# EMI_EMC_schematic.net
KiCad netlist of a schematic drawn in Altium Designer
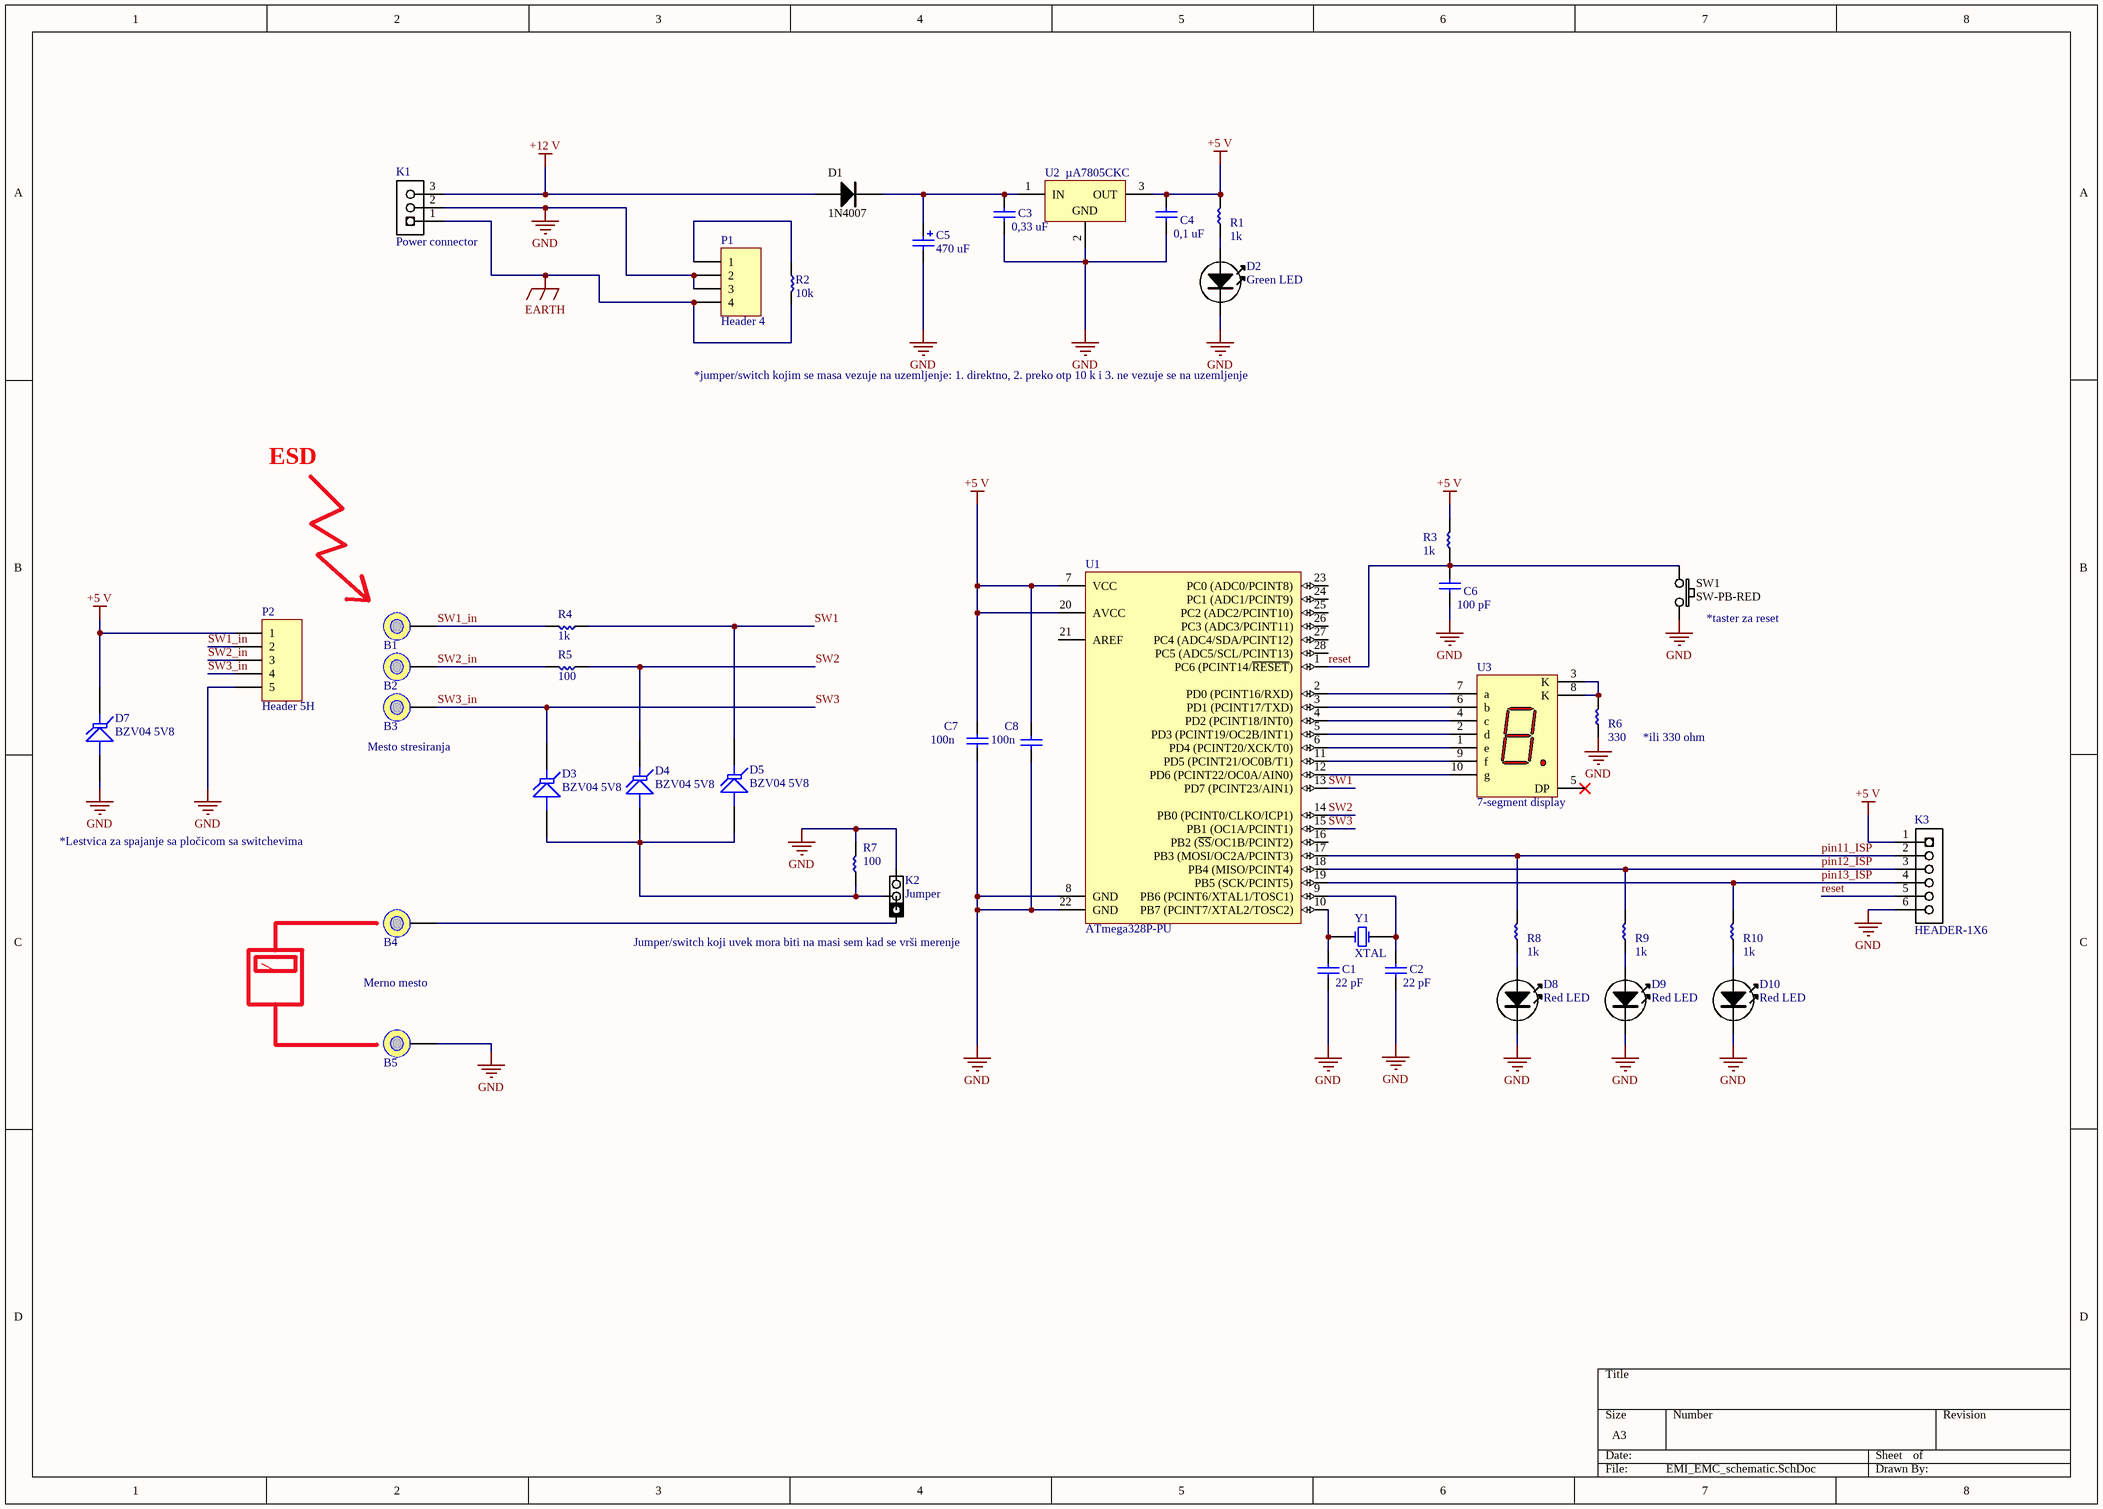
[diagram p0: EMI_EMC_schematic.SchDoc]

(export (version "E")
  (design (tool "Eeschema 10.0.6"))
  (components
    (comp (ref "B1")
      (value "Buksna 4mm")
      (footprint "Buksna 4mm")
      (libsource (lib "EMI_SCH_lib") (part "Buksna"))
    )
    (comp (ref "B2")
      (value "Buksna 4mm")
      (footprint "Buksna 4mm")
      (libsource (lib "EMI_SCH_lib") (part "Buksna"))
    )
    (comp (ref "B3")
      (value "Buksna 4mm")
      (footprint "Buksna 4mm")
      (libsource (lib "EMI_SCH_lib") (part "Buksna"))
    )
    (comp (ref "B4")
      (value "Buksna 4mm")
      (footprint "Buksna 4mm")
      (libsource (lib "EMI_SCH_lib") (part "Buksna"))
    )
    (comp (ref "B5")
      (value "Buksna 4mm")
      (footprint "Buksna 4mm")
      (libsource (lib "EMI_SCH_lib") (part "Buksna"))
    )
    (comp (ref "C1")
      (value "22 pF")
      (footprint "Cap_100mil")
      (fields (field (name "Comment") "Cap"))
      (libsource (lib "my_library") (part "Cap"))
    )
    (comp (ref "C2")
      (value "22 pF")
      (footprint "Cap_100mil")
      (fields (field (name "Comment") "Cap"))
      (libsource (lib "my_library") (part "Cap"))
    )
    (comp (ref "C3")
      (value "0,33 uF")
      (footprint "Cap_100mil")
      (fields (field (name "Comment") "Cap"))
      (libsource (lib "my_library") (part "Cap"))
    )
    (comp (ref "C4")
      (value "0,1 uF")
      (footprint "Cap_100mil")
      (fields (field (name "Comment") "Cap"))
      (libsource (lib "my_library") (part "Cap"))
    )
    (comp (ref "C5")
      (value "470 uF")
      (footprint "Cap Pol 1000 uF")
      (fields (field (name "Comment") "Cap_pol"))
      (libsource (lib "EMI_SCH_lib") (part "Cap_pol"))
    )
    (comp (ref "C6")
      (value "100 pF")
      (footprint "Cap_100mil")
      (fields (field (name "Comment") "Cap"))
      (libsource (lib "my_library") (part "Cap"))
    )
    (comp (ref "C7")
      (value "100n")
      (footprint "Cap_100mil")
      (fields (field (name "Comment") "Cap"))
      (libsource (lib "my_library") (part "Cap"))
    )
    (comp (ref "C8")
      (value "100n")
      (footprint "Cap_100mil")
      (fields (field (name "Comment") "Cap"))
      (libsource (lib "my_library") (part "Cap"))
    )
    (comp (ref "D1")
      (value "1N4007")
      (footprint "1N400X")
      (description "1N4001")
      (libsource (lib "vh_altium_library") (part "1N4001"))
    )
    (comp (ref "D2")
      (value "Green LED")
      (footprint "LED-5MM-GREEN")
      (description "LED-GREEN-5MM")
      (libsource (lib "vh_altium_library") (part "LED-GREEN-5MM"))
    )
    (comp (ref "D3")
      (value "TVS diode")
      (footprint "TVS DO - 7")
      (fields (field (name "PART NAME") "BZV04 5V8"))
      (libsource (lib "EMI_SCH_lib") (part "TVS diode"))
    )
    (comp (ref "D4")
      (value "TVS diode")
      (footprint "TVS DO - 7")
      (fields (field (name "PART NAME") "BZV04 5V8"))
      (libsource (lib "EMI_SCH_lib") (part "TVS diode"))
    )
    (comp (ref "D5")
      (value "TVS diode")
      (footprint "TVS DO - 7")
      (fields (field (name "PART NAME") "BZV04 5V8"))
      (libsource (lib "EMI_SCH_lib") (part "TVS diode"))
    )
    (comp (ref "D7")
      (value "TVS diode")
      (footprint "TVS DO - 7")
      (fields (field (name "PART NAME") "BZV04 5V8"))
      (libsource (lib "EMI_SCH_lib") (part "TVS diode"))
    )
    (comp (ref "D8")
      (value "Red LED")
      (footprint "LED-5MM-RED")
      (description "LED-RED-5MM")
      (libsource (lib "vh_altium_library") (part "LED-RED-5MM"))
    )
    (comp (ref "D9")
      (value "Red LED")
      (footprint "LED-5MM-RED")
      (description "LED-RED-5MM")
      (libsource (lib "vh_altium_library") (part "LED-RED-5MM"))
    )
    (comp (ref "D10")
      (value "Red LED")
      (footprint "LED-5MM-RED")
      (description "LED-RED-5MM")
      (libsource (lib "vh_altium_library") (part "LED-RED-5MM"))
    )
    (comp (ref "K1")
      (value "Power connector")
      (footprint "Header for power")
      (libsource (lib "EMI_SCH_lib") (part "Power connector"))
    )
    (comp (ref "K2")
      (value "Jumper")
      (footprint "JMPR3-CLOSED-12")
      (description "JMPR3")
      (fields
        (field (name "MANUFACTURER") "Sullins Connector Solutions")
        (field (name "MANUFACTURER PART NUMBER") "PBC36SAAN")
      )
      (libsource (lib "TH Connectors") (part "JMPR3-12"))
    )
    (comp (ref "K3")
      (value "HEADER-1X6")
      (footprint "HEADER-1X6")
      (libsource (lib "TH Connectors") (part "HEADER-1X6"))
    )
    (comp (ref "P1")
      (value "Header 4")
      (footprint "HDR1X4")
      (description "Header, 4-Pin")
      (fields (field (name "PUBLISHER") "Altium Limited"))
      (libsource (lib "Miscellaneous Connectors") (part "Header 4"))
    )
    (comp (ref "P2")
      (value "Header 5H")
      (footprint "HDR1X5H")
      (description "Header, 5-Pin, Right Angle")
      (fields (field (name "PUBLISHER") "Altium Limited"))
      (libsource (lib "Miscellaneous Connectors") (part "Header 5H"))
    )
    (comp (ref "R1")
      (value "1k")
      (footprint "Res_axial 0.4")
      (fields (field (name "Comment") "res_0,25w"))
      (libsource (lib "my_library") (part "Res_axial0.4"))
    )
    (comp (ref "R2")
      (value "10k")
      (footprint "Res_axial 0.4")
      (fields (field (name "Comment") "res_0,25w"))
      (libsource (lib "my_library") (part "Res_axial0.4"))
    )
    (comp (ref "R3")
      (value "1k")
      (footprint "Res_axial 0.4")
      (fields (field (name "Comment") "res_0,25w"))
      (libsource (lib "my_library") (part "Res_axial0.4"))
    )
    (comp (ref "R4")
      (value "1k")
      (footprint "Res_axial 0.4")
      (fields (field (name "Comment") "res_0,25w"))
      (libsource (lib "my_library") (part "Res_axial0.4"))
    )
    (comp (ref "R5")
      (value "100")
      (footprint "Res_axial 0.4")
      (fields (field (name "Comment") "res_0,25w"))
      (libsource (lib "my_library") (part "Res_axial0.4"))
    )
    (comp (ref "R6")
      (value "330")
      (footprint "Res_axial 0.4")
      (fields (field (name "Comment") "res_0,25w"))
      (libsource (lib "my_library") (part "Res_axial0.4"))
    )
    (comp (ref "R7")
      (value "100")
      (footprint "Res_axial 0.4")
      (fields (field (name "Comment") "res_0,25w"))
      (libsource (lib "my_library") (part "Res_axial0.4"))
    )
    (comp (ref "R8")
      (value "1k")
      (footprint "Res_axial 0.4")
      (fields (field (name "Comment") "res_0,25w"))
      (libsource (lib "my_library") (part "Res_axial0.4"))
    )
    (comp (ref "R9")
      (value "1k")
      (footprint "Res_axial 0.4")
      (fields (field (name "Comment") "res_0,25w"))
      (libsource (lib "my_library") (part "Res_axial0.4"))
    )
    (comp (ref "R10")
      (value "1k")
      (footprint "Res_axial 0.4")
      (fields (field (name "Comment") "res_0,25w"))
      (libsource (lib "my_library") (part "Res_axial0.4"))
    )
    (comp (ref "SW1")
      (value "SW-PB-RED")
      (footprint "SW-PB-RED-ROUND4")
      (description "SW-D6-R / SW-DS-S / SW-14X14 / SW-7X7")
      (libsource (lib "vh_altium_library") (part "SW-PB-RED"))
    )
    (comp (ref "U1")
      (value "ATmega328P-PU")
      (footprint "28P3")
      (fields (field (name "PUBLISHER") "Altium Limited"))
      (libsource (lib "Atmel Microcontroller 8-Bit megaAVR") (part "ATmega328P-PU"))
    )
    (comp (ref "U2") (value "µA7805CKC") (footprint "TO220") (libsource (lib "my_library") (part "TO220")))
    (comp (ref "U3")
      (value "7-segment display")
      (footprint "7-segment disp")
      (libsource (lib "EMI_SCH_lib") (part "7-segment"))
    )
    (comp (ref "Y1") (value "XTAL") (footprint "xtal") (libsource (lib "EMI_SCH_lib") (part "XTAL")))
  )
  (nets
    (net (code "1") (name "+5 V") (class "Default")
      (node (ref "C4") (pin "1") (pinfunction "1_1") (pintype "passive"))
      (node (ref "C7") (pin "2") (pinfunction "2_2") (pintype "passive"))
      (node (ref "C8") (pin "2") (pinfunction "2_2") (pintype "passive"))
      (node (ref "D7") (pin "2") (pinfunction "K_2") (pintype "passive"))
      (node (ref "K3") (pin "1") (pintype "passive"))
      (node (ref "P2") (pin "1") (pinfunction "1_1") (pintype "passive"))
      (node (ref "R1") (pin "2") (pinfunction "2_2") (pintype "passive"))
      (node (ref "R3") (pin "2") (pinfunction "2_2") (pintype "passive"))
      (node (ref "U1") (pin "20") (pinfunction "AVCC_20") (pintype "power_in"))
      (node (ref "U1") (pin "7") (pinfunction "VCC_7") (pintype "power_in"))
      (node (ref "U2") (pin "3") (pinfunction "OUT_3") (pintype "power_in"))
    )
    (net (code "2") (name "+12 V") (class "Default")
      (node (ref "D1") (pin "A") (pinfunction "A_A") (pintype "passive"))
      (node (ref "K1") (pin "3") (pintype "passive"))
    )
    (net (code "3") (name "/SW1") (class "Default")
      (node (ref "D5") (pin "2") (pinfunction "K_2") (pintype "passive"))
      (node (ref "R4") (pin "1") (pinfunction "1_1") (pintype "passive"))
      (node (ref "U1") (pin "13") (pinfunction "PD7_(PCINT23/AIN1)_13") (pintype "bidirectional"))
    )
    (net (code "4") (name "/SW1_in") (class "Default")
      (node (ref "B1") (pin "1") (pinfunction "1_1") (pintype "passive"))
      (node (ref "P2") (pin "2") (pinfunction "2_2") (pintype "passive"))
      (node (ref "R4") (pin "2") (pinfunction "2_2") (pintype "passive"))
    )
    (net (code "5") (name "/SW2") (class "Default")
      (node (ref "D4") (pin "2") (pinfunction "K_2") (pintype "passive"))
      (node (ref "R5") (pin "1") (pinfunction "1_1") (pintype "passive"))
      (node (ref "U1") (pin "14") (pinfunction "PB0_(PCINT0/CLKO/ICP1)_14") (pintype "bidirectional"))
    )
    (net (code "6") (name "/SW2_in") (class "Default")
      (node (ref "B2") (pin "1") (pinfunction "1_1") (pintype "passive"))
      (node (ref "P2") (pin "3") (pinfunction "3_3") (pintype "passive"))
      (node (ref "R5") (pin "2") (pinfunction "2_2") (pintype "passive"))
    )
    (net (code "7") (name "/SW3") (class "Default")
      (node (ref "B3") (pin "1") (pinfunction "1_1") (pintype "passive"))
      (node (ref "D3") (pin "2") (pinfunction "K_2") (pintype "passive"))
      (node (ref "P2") (pin "4") (pinfunction "4_4") (pintype "passive"))
      (node (ref "U1") (pin "15") (pinfunction "PB1_(OC1A/PCINT1)_15") (pintype "bidirectional"))
    )
    (net (code "8") (name "/pin11_ISP") (class "Default")
      (node (ref "K3") (pin "2") (pintype "passive"))
      (node (ref "R8") (pin "2") (pinfunction "2_2") (pintype "passive"))
      (node (ref "U1") (pin "17") (pinfunction "PB3_(MOSI/OC2A/PCINT3)_17") (pintype "bidirectional"))
    )
    (net (code "9") (name "/pin12_ISP") (class "Default")
      (node (ref "K3") (pin "3") (pintype "passive"))
      (node (ref "R9") (pin "2") (pinfunction "2_2") (pintype "passive"))
      (node (ref "U1") (pin "18") (pinfunction "PB4_(MISO/PCINT4)_18") (pintype "bidirectional"))
    )
    (net (code "10") (name "/pin13_ISP") (class "Default")
      (node (ref "K3") (pin "4") (pintype "passive"))
      (node (ref "R10") (pin "2") (pinfunction "2_2") (pintype "passive"))
      (node (ref "U1") (pin "19") (pinfunction "PB5_(SCK/PCINT5)_19") (pintype "bidirectional"))
    )
    (net (code "11") (name "/reset") (class "Default")
      (node (ref "C6") (pin "1") (pinfunction "1_1") (pintype "passive"))
      (node (ref "K3") (pin "5") (pintype "passive"))
      (node (ref "R3") (pin "1") (pinfunction "1_1") (pintype "passive"))
      (node (ref "SW1") (pin "1") (pintype "passive"))
      (node (ref "U1") (pin "1") (pinfunction "PC6_(PCINT14/~{RESET})_1") (pintype "bidirectional"))
    )
    (net (code "12") (name "EARTH") (class "Default")
      (node (ref "K1") (pin "1") (pintype "passive"))
      (node (ref "P1") (pin "4") (pinfunction "4_4") (pintype "passive"))
      (node (ref "R2") (pin "2") (pinfunction "2_2") (pintype "passive"))
    )
    (net (code "13") (name "GND") (class "Default")
      (node (ref "B5") (pin "1") (pinfunction "1_1") (pintype "passive"))
      (node (ref "C1") (pin "2") (pinfunction "2_2") (pintype "passive"))
      (node (ref "C2") (pin "2") (pinfunction "2_2") (pintype "passive"))
      (node (ref "C3") (pin "2") (pinfunction "2_2") (pintype "passive"))
      (node (ref "C4") (pin "2") (pinfunction "2_2") (pintype "passive"))
      (node (ref "C5") (pin "2") (pinfunction "2_2") (pintype "passive"))
      (node (ref "C6") (pin "2") (pinfunction "2_2") (pintype "passive"))
      (node (ref "C7") (pin "1") (pinfunction "1_1") (pintype "passive"))
      (node (ref "C8") (pin "1") (pinfunction "1_1") (pintype "passive"))
      (node (ref "D10") (pin "K") (pintype "passive"))
      (node (ref "D2") (pin "K") (pintype "passive"))
      (node (ref "D7") (pin "1") (pinfunction "A_1") (pintype "passive"))
      (node (ref "D8") (pin "K") (pintype "passive"))
      (node (ref "D9") (pin "K") (pintype "passive"))
      (node (ref "K1") (pin "2") (pintype "passive"))
      (node (ref "K2") (pin "3") (pintype "passive"))
      (node (ref "K3") (pin "6") (pintype "passive"))
      (node (ref "P1") (pin "2") (pinfunction "2_2") (pintype "passive"))
      (node (ref "P1") (pin "3") (pinfunction "3_3") (pintype "passive"))
      (node (ref "P2") (pin "5") (pinfunction "5_5") (pintype "passive"))
      (node (ref "R6") (pin "1") (pinfunction "1_1") (pintype "passive"))
      (node (ref "R7") (pin "2") (pinfunction "2_2") (pintype "passive"))
      (node (ref "SW1") (pin "2") (pintype "passive"))
      (node (ref "U1") (pin "22") (pinfunction "GND_22") (pintype "power_in"))
      (node (ref "U1") (pin "8") (pinfunction "GND_8") (pintype "power_in"))
      (node (ref "U2") (pin "2") (pinfunction "GND_2") (pintype "power_in"))
    )
    (net (code "14") (name "Net-(B4-Pad1)") (class "Default")
      (node (ref "B4") (pin "1") (pinfunction "1_1") (pintype "passive"))
      (node (ref "K2") (pin "1") (pintype "passive"))
    )
    (net (code "15") (name "Net-(D2-PadA)") (class "Default")
      (node (ref "D2") (pin "A") (pintype "passive"))
      (node (ref "R1") (pin "1") (pinfunction "1_1") (pintype "passive"))
    )
    (net (code "16") (name "Net-(D3-A)") (class "Default")
      (node (ref "D3") (pin "1") (pinfunction "A_1") (pintype "passive"))
      (node (ref "D4") (pin "1") (pinfunction "A_1") (pintype "passive"))
      (node (ref "D5") (pin "1") (pinfunction "A_1") (pintype "passive"))
      (node (ref "K2") (pin "2") (pintype "passive"))
      (node (ref "R7") (pin "1") (pinfunction "1_1") (pintype "passive"))
    )
    (net (code "17") (name "Net-(D8-PadA)") (class "Default")
      (node (ref "D8") (pin "A") (pintype "passive"))
      (node (ref "R8") (pin "1") (pinfunction "1_1") (pintype "passive"))
    )
    (net (code "18") (name "Net-(D9-PadA)") (class "Default")
      (node (ref "D9") (pin "A") (pintype "passive"))
      (node (ref "R9") (pin "1") (pinfunction "1_1") (pintype "passive"))
    )
    (net (code "19") (name "Net-(D10-PadA)") (class "Default")
      (node (ref "D10") (pin "A") (pintype "passive"))
      (node (ref "R10") (pin "1") (pinfunction "1_1") (pintype "passive"))
    )
    (net (code "20") (name "Net-(P1-Pad1)") (class "Default")
      (node (ref "P1") (pin "1") (pinfunction "1_1") (pintype "passive"))
      (node (ref "R2") (pin "1") (pinfunction "1_1") (pintype "passive"))
    )
    (net (code "21") (name "Net-(R6-Pad2)") (class "Default")
      (node (ref "R6") (pin "2") (pinfunction "2_2") (pintype "passive"))
      (node (ref "U3") (pin "3") (pinfunction "K_3") (pintype "passive"))
      (node (ref "U3") (pin "8") (pinfunction "K_8") (pintype "passive"))
    )
    (net (code "22") (name "Net-(U1-PB6_(PCINT6{slash}XTAL1{slash}TOSC1))") (class "Default")
      (node (ref "C2") (pin "1") (pinfunction "1_1") (pintype "passive"))
      (node (ref "U1") (pin "9") (pinfunction "PB6_(PCINT6/XTAL1/TOSC1)_9") (pintype "bidirectional"))
      (node (ref "Y1") (pin "2") (pinfunction "OSC2_2") (pintype "passive"))
    )
    (net (code "23") (name "Net-(U1-PB7_(PCINT7{slash}XTAL2{slash}TOSC2))") (class "Default")
      (node (ref "C1") (pin "1") (pinfunction "1_1") (pintype "passive"))
      (node (ref "U1") (pin "10") (pinfunction "PB7_(PCINT7/XTAL2/TOSC2)_10") (pintype "bidirectional"))
      (node (ref "Y1") (pin "1") (pinfunction "OSC1_1") (pintype "passive"))
    )
    (net (code "24") (name "Net-(U1-PD0_(PCINT16{slash}RXD))") (class "Default")
      (node (ref "U1") (pin "2") (pinfunction "PD0_(PCINT16/RXD)_2") (pintype "bidirectional"))
      (node (ref "U3") (pin "7") (pinfunction "a_7") (pintype "passive"))
    )
    (net (code "25") (name "Net-(U1-PD1_(PCINT17{slash}TXD))") (class "Default")
      (node (ref "U1") (pin "3") (pinfunction "PD1_(PCINT17/TXD)_3") (pintype "bidirectional"))
      (node (ref "U3") (pin "6") (pinfunction "b_6") (pintype "passive"))
    )
    (net (code "26") (name "Net-(U1-PD2_(PCINT18{slash}INT0))") (class "Default")
      (node (ref "U1") (pin "4") (pinfunction "PD2_(PCINT18/INT0)_4") (pintype "bidirectional"))
      (node (ref "U3") (pin "4") (pinfunction "c_4") (pintype "passive"))
    )
    (net (code "27") (name "Net-(U1-PD3_(PCINT19{slash}OC2B{slash}INT1))") (class "Default")
      (node (ref "U1") (pin "5") (pinfunction "PD3_(PCINT19/OC2B/INT1)_5") (pintype "bidirectional"))
      (node (ref "U3") (pin "2") (pinfunction "d_2") (pintype "passive"))
    )
    (net (code "28") (name "Net-(U1-PD4_(PCINT20{slash}XCK{slash}T0))") (class "Default")
      (node (ref "U1") (pin "6") (pinfunction "PD4_(PCINT20/XCK/T0)_6") (pintype "bidirectional"))
      (node (ref "U3") (pin "1") (pinfunction "e_1") (pintype "passive"))
    )
    (net (code "29") (name "Net-(U1-PD5_(PCINT21{slash}OC0B{slash}T1))") (class "Default")
      (node (ref "U1") (pin "11") (pinfunction "PD5_(PCINT21/OC0B/T1)_11") (pintype "bidirectional"))
      (node (ref "U3") (pin "9") (pinfunction "f_9") (pintype "passive"))
    )
    (net (code "30") (name "Net-(U1-PD6_(PCINT22{slash}OC0A{slash}AIN0))") (class "Default")
      (node (ref "U1") (pin "12") (pinfunction "PD6_(PCINT22/OC0A/AIN0)_12") (pintype "bidirectional"))
      (node (ref "U3") (pin "10") (pinfunction "g_10") (pintype "passive"))
    )
    (net (code "31") (name "Net-(U2-IN)") (class "Default")
      (node (ref "C3") (pin "1") (pinfunction "1_1") (pintype "passive"))
      (node (ref "C5") (pin "1") (pinfunction "1_1") (pintype "passive"))
      (node (ref "D1") (pin "K") (pinfunction "K_K") (pintype "passive"))
      (node (ref "U2") (pin "1") (pinfunction "IN_1") (pintype "power_in"))
    )
    (net (code "32") (name "unconnected-(B1-Pad2)") (class "Default")
      (node (ref "B1") (pin "2") (pinfunction "2_2") (pintype "passive"))
    )
    (net (code "33") (name "unconnected-(B2-Pad2)") (class "Default")
      (node (ref "B2") (pin "2") (pinfunction "2_2") (pintype "passive"))
    )
    (net (code "34") (name "unconnected-(B3-Pad2)") (class "Default")
      (node (ref "B3") (pin "2") (pinfunction "2_2") (pintype "passive"))
    )
    (net (code "35") (name "unconnected-(B4-Pad2)") (class "Default")
      (node (ref "B4") (pin "2") (pinfunction "2_2") (pintype "passive"))
    )
    (net (code "36") (name "unconnected-(B5-Pad2)") (class "Default")
      (node (ref "B5") (pin "2") (pinfunction "2_2") (pintype "passive"))
    )
    (net (code "37") (name "unconnected-(U1-AREF-Pad21)") (class "Default")
      (node (ref "U1") (pin "21") (pinfunction "AREF_21") (pintype "power_in"))
    )
    (net (code "38") (name "unconnected-(U1-PB2_(~{SS}{slash}OC1B{slash}PCINT2)-Pad16)") (class "Default")
      (node (ref "U1") (pin "16") (pinfunction "PB2_(~{SS}/OC1B/PCINT2)_16") (pintype "bidirectional"))
    )
    (net (code "39") (name "unconnected-(U1-PC0_(ADC0{slash}PCINT8)-Pad23)") (class "Default")
      (node (ref "U1") (pin "23") (pinfunction "PC0_(ADC0/PCINT8)_23") (pintype "bidirectional"))
    )
    (net (code "40") (name "unconnected-(U1-PC1_(ADC1{slash}PCINT9)-Pad24)") (class "Default")
      (node (ref "U1") (pin "24") (pinfunction "PC1_(ADC1/PCINT9)_24") (pintype "bidirectional"))
    )
    (net (code "41") (name "unconnected-(U1-PC2_(ADC2{slash}PCINT10)-Pad25)") (class "Default")
      (node (ref "U1") (pin "25") (pinfunction "PC2_(ADC2/PCINT10)_25") (pintype "bidirectional"))
    )
    (net (code "42") (name "unconnected-(U1-PC3_(ADC3{slash}PCINT11)-Pad26)") (class "Default")
      (node (ref "U1") (pin "26") (pinfunction "PC3_(ADC3/PCINT11)_26") (pintype "bidirectional"))
    )
    (net (code "43") (name "unconnected-(U1-PC4_(ADC4{slash}SDA{slash}PCINT12)-Pad27)") (class "Default")
      (node (ref "U1") (pin "27") (pinfunction "PC4_(ADC4/SDA/PCINT12)_27") (pintype "bidirectional"))
    )
    (net (code "44") (name "unconnected-(U1-PC5_(ADC5{slash}SCL{slash}PCINT13)-Pad28)") (class "Default")
      (node (ref "U1") (pin "28") (pinfunction "PC5_(ADC5/SCL/PCINT13)_28") (pintype "bidirectional"))
    )
    (net (code "45") (name "unconnected-(U3-DP-Pad5)") (class "Default")
      (node (ref "U3") (pin "5") (pinfunction "DP_5") (pintype "passive+no_connect"))
    )
  )
)
